# one_wire_com_board.net
KiCad netlist of a schematic drawn in EAGLE
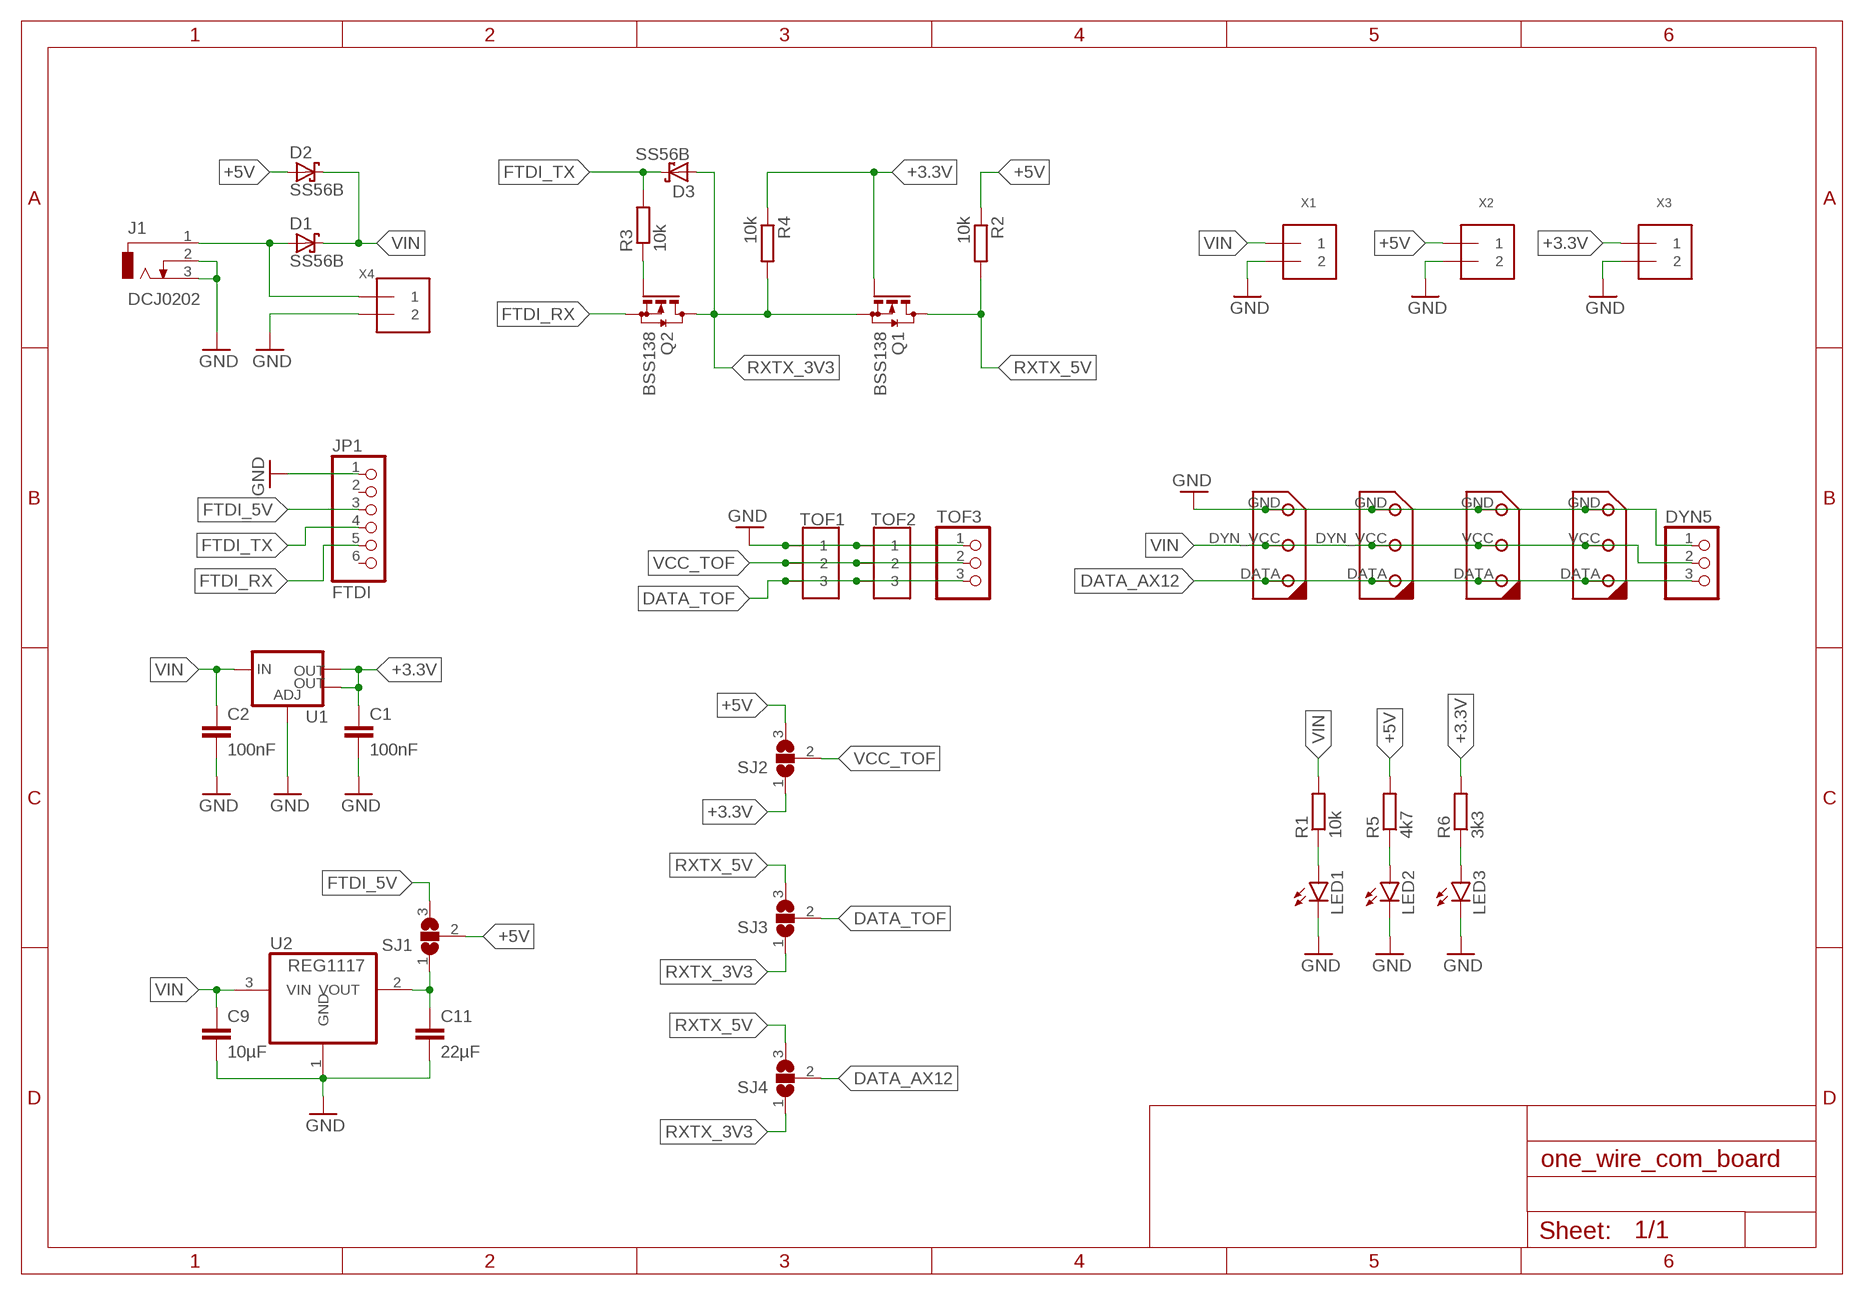
[diagram p0: schematic, sheet 1]

(export (version "E")
  (design (tool "Eeschema 10.0.6"))
  (components
    (comp (ref "C1")
      (value "100nF")
      (footprint "eagle-import:C0805")
      (libsource (lib "eagle-import") (part "C-EUC0805"))
    )
    (comp (ref "C2")
      (value "100nF")
      (footprint "eagle-import:C0805")
      (libsource (lib "eagle-import") (part "C-EUC0805"))
    )
    (comp (ref "C9")
      (value "10µF")
      (footprint "eagle-import:C0805")
      (libsource (lib "eagle-import") (part "resistor_348_C-EUC0805"))
    )
    (comp (ref "C11")
      (value "22µF")
      (footprint "eagle-import:C0805")
      (libsource (lib "eagle-import") (part "resistor_348_C-EUC0805"))
    )
    (comp (ref "D1")
      (value "SS56B")
      (footprint "eagle-import:SMB")
      (libsource (lib "eagle-import") (part "SCHOTTKY-DIODESMD"))
    )
    (comp (ref "D2")
      (value "SS56B")
      (footprint "eagle-import:SMB")
      (libsource (lib "eagle-import") (part "SCHOTTKY-DIODESMD"))
    )
    (comp (ref "D3")
      (value "SS56B")
      (footprint "eagle-import:SMB")
      (libsource (lib "eagle-import") (part "SCHOTTKY-DIODESMD"))
    )
    (comp (ref "DYN1")
      (value "DYNAMIXEL-1X03AX")
      (footprint "eagle-import:DYNAMIXEL_AX_1X03")
      (libsource (lib "eagle-import") (part "DYNAMIXEL-1X03AX"))
    )
    (comp (ref "DYN2")
      (value "DYNAMIXEL-1X03AX")
      (footprint "eagle-import:DYNAMIXEL_AX_1X03")
      (libsource (lib "eagle-import") (part "DYNAMIXEL-1X03AX"))
    )
    (comp (ref "DYN3")
      (value "DYNAMIXEL-1X03XL")
      (footprint "eagle-import:DYNAMIXEL_XL_1X03")
      (libsource (lib "eagle-import") (part "DYNAMIXEL-1X03XL"))
    )
    (comp (ref "DYN4")
      (value "DYNAMIXEL-1X03XL")
      (footprint "eagle-import:DYNAMIXEL_XL_1X03")
      (libsource (lib "eagle-import") (part "DYNAMIXEL-1X03XL"))
    )
    (comp (ref "DYN5")
      (value "PINHD-1X3")
      (footprint "eagle-import:1X03")
      (libsource (lib "eagle-import") (part "PINHD-1X3"))
    )
    (comp (ref "J1")
      (value "DCJ0202")
      (footprint "eagle-import:DCJ0202")
      (libsource (lib "eagle-import") (part "DCJ0202"))
    )
    (comp (ref "JP1")
      (value "FTDI")
      (footprint "eagle-import:1X06_90")
      (libsource (lib "eagle-import") (part "PINHD-1X6/90"))
    )
    (comp (ref "LED1")
      (value "LEDSMT1206")
      (footprint "eagle-import:1206")
      (libsource (lib "eagle-import") (part "LEDSMT1206"))
    )
    (comp (ref "LED2")
      (value "LEDSMT1206")
      (footprint "eagle-import:1206")
      (libsource (lib "eagle-import") (part "LEDSMT1206"))
    )
    (comp (ref "LED3")
      (value "LEDSMT1206")
      (footprint "eagle-import:1206")
      (libsource (lib "eagle-import") (part "LEDSMT1206"))
    )
    (comp (ref "Q1")
      (value "BSS138")
      (footprint "eagle-import:SOT23")
      (libsource (lib "eagle-import") (part "BSS123"))
    )
    (comp (ref "Q2")
      (value "BSS138")
      (footprint "eagle-import:SOT23")
      (libsource (lib "eagle-import") (part "BSS123"))
    )
    (comp (ref "R1")
      (value "10k")
      (footprint "eagle-import:R0805")
      (libsource (lib "eagle-import") (part "R-EU_R0805"))
    )
    (comp (ref "R2")
      (value "10k")
      (footprint "eagle-import:R0805")
      (libsource (lib "eagle-import") (part "R-EU_R0805"))
    )
    (comp (ref "R3")
      (value "10k")
      (footprint "eagle-import:R0805")
      (libsource (lib "eagle-import") (part "R-EU_R0805"))
    )
    (comp (ref "R4")
      (value "10k")
      (footprint "eagle-import:R0805")
      (libsource (lib "eagle-import") (part "R-EU_R0805"))
    )
    (comp (ref "R5")
      (value "4k7")
      (footprint "eagle-import:R0805")
      (libsource (lib "eagle-import") (part "R-EU_R0805"))
    )
    (comp (ref "R6")
      (value "3k3")
      (footprint "eagle-import:R0805")
      (libsource (lib "eagle-import") (part "R-EU_R0805"))
    )
    (comp (ref "SJ1")
      (value "SJ2W")
      (footprint "eagle-import:SJ_2")
      (libsource (lib "eagle-import") (part "SJ2W"))
    )
    (comp (ref "SJ2")
      (value "SJ2W")
      (footprint "eagle-import:SJ_2")
      (libsource (lib "eagle-import") (part "SJ2W"))
    )
    (comp (ref "SJ3")
      (value "SJ2W")
      (footprint "eagle-import:SJ_2")
      (libsource (lib "eagle-import") (part "SJ2W"))
    )
    (comp (ref "SJ4")
      (value "SJ2W")
      (footprint "eagle-import:SJ_2")
      (libsource (lib "eagle-import") (part "SJ2W"))
    )
    (comp (ref "TOF1")
      (value "JST-03")
      (footprint "eagle-import:GH-03-V")
      (libsource (lib "eagle-import") (part "JST-03"))
    )
    (comp (ref "TOF2")
      (value "JST-03")
      (footprint "eagle-import:GH-03-V")
      (libsource (lib "eagle-import") (part "JST-03"))
    )
    (comp (ref "TOF3")
      (value "PINHD-1X3")
      (footprint "eagle-import:1X03")
      (libsource (lib "eagle-import") (part "PINHD-1X3"))
    )
    (comp (ref "U1")
      (value "V_REG_LM1117SOT223")
      (footprint "eagle-import:SOT223")
      (libsource (lib "eagle-import") (part "V_REG_LM1117SOT223"))
    )
    (comp (ref "U2")
      (value "REG1117")
      (footprint "eagle-import:SOT223")
      (libsource (lib "eagle-import") (part "REG1117"))
    )
    (comp (ref "X1")
      (value "TERMBLOCK_1X2")
      (footprint "eagle-import:TERMBLOCK_1X2-3.5MM")
      (libsource (lib "eagle-import") (part "TERMBLOCK_1X2"))
    )
    (comp (ref "X2")
      (value "TERMBLOCK_1X2")
      (footprint "eagle-import:TERMBLOCK_1X2-3.5MM")
      (libsource (lib "eagle-import") (part "TERMBLOCK_1X2"))
    )
    (comp (ref "X3")
      (value "TERMBLOCK_1X2")
      (footprint "eagle-import:TERMBLOCK_1X2-3.5MM")
      (libsource (lib "eagle-import") (part "TERMBLOCK_1X2"))
    )
    (comp (ref "X4")
      (value "TERMBLOCK_1X2")
      (footprint "eagle-import:TERMBLOCK_1X2-3.5MM")
      (libsource (lib "eagle-import") (part "TERMBLOCK_1X2"))
    )
  )
  (nets
    (net (code "1") (name "+3.3V") (class "Default")
      (node (ref "C1") (pin "1") (pinfunction "1_1") (pintype "passive"))
      (node (ref "Q1") (pin "1") (pinfunction "G_1") (pintype "passive"))
      (node (ref "R4") (pin "1") (pinfunction "1_1") (pintype "passive"))
      (node (ref "R6") (pin "2") (pinfunction "2_2") (pintype "passive"))
      (node (ref "SJ2") (pin "1") (pinfunction "1_1") (pintype "passive"))
      (node (ref "U1") (pin "2") (pinfunction "OUT_2") (pintype "output"))
      (node (ref "U1") (pin "4") (pinfunction "OUT_4") (pintype "output"))
      (node (ref "X3") (pin "1") (pinfunction "1_1") (pintype "passive"))
    )
    (net (code "2") (name "+5V") (class "Default")
      (node (ref "D2") (pin "A") (pinfunction "A_A") (pintype "passive"))
      (node (ref "R2") (pin "1") (pinfunction "1_1") (pintype "passive"))
      (node (ref "R5") (pin "2") (pinfunction "2_2") (pintype "passive"))
      (node (ref "SJ1") (pin "2") (pinfunction "2_2") (pintype "passive"))
      (node (ref "SJ2") (pin "3") (pinfunction "3_3") (pintype "passive"))
      (node (ref "X2") (pin "1") (pinfunction "1_1") (pintype "passive"))
    )
    (net (code "3") (name "DATA_AX12") (class "Default")
      (node (ref "DYN1") (pin "DATA") (pinfunction "DATA_DATA") (pintype "bidirectional"))
      (node (ref "DYN2") (pin "DATA") (pinfunction "DATA_DATA") (pintype "bidirectional"))
      (node (ref "DYN3") (pin "DATA") (pinfunction "DATA_DATA") (pintype "bidirectional"))
      (node (ref "DYN4") (pin "DATA") (pinfunction "DATA_DATA") (pintype "bidirectional"))
      (node (ref "DYN5") (pin "3") (pinfunction "3_3") (pintype "passive"))
      (node (ref "SJ4") (pin "2") (pinfunction "2_2") (pintype "passive"))
    )
    (net (code "4") (name "DATA_TOF") (class "Default")
      (node (ref "SJ3") (pin "2") (pinfunction "2_2") (pintype "passive"))
      (node (ref "TOF1") (pin "3") (pinfunction "3_3") (pintype "bidirectional"))
      (node (ref "TOF2") (pin "3") (pinfunction "3_3") (pintype "bidirectional"))
      (node (ref "TOF3") (pin "3") (pinfunction "3_3") (pintype "passive"))
    )
    (net (code "5") (name "FTDI_5V") (class "Default")
      (node (ref "JP1") (pin "3") (pinfunction "3_3") (pintype "passive"))
      (node (ref "SJ1") (pin "3") (pinfunction "3_3") (pintype "passive"))
    )
    (net (code "6") (name "FTDI_RX") (class "Default")
      (node (ref "JP1") (pin "5") (pinfunction "5_5") (pintype "passive"))
      (node (ref "Q2") (pin "2") (pinfunction "S_2") (pintype "passive"))
    )
    (net (code "7") (name "FTDI_TX") (class "Default")
      (node (ref "D3") (pin "C") (pinfunction "C_C") (pintype "passive"))
      (node (ref "JP1") (pin "4") (pinfunction "4_4") (pintype "passive"))
      (node (ref "R3") (pin "2") (pinfunction "2_2") (pintype "passive"))
    )
    (net (code "8") (name "GND") (class "Default")
      (node (ref "C1") (pin "2") (pinfunction "2_2") (pintype "passive"))
      (node (ref "C11") (pin "2") (pinfunction "2_2") (pintype "passive"))
      (node (ref "C2") (pin "2") (pinfunction "2_2") (pintype "passive"))
      (node (ref "C9") (pin "2") (pinfunction "2_2") (pintype "passive"))
      (node (ref "DYN1") (pin "GND") (pinfunction "GND_GND") (pintype "power_in"))
      (node (ref "DYN2") (pin "GND") (pinfunction "GND_GND") (pintype "power_in"))
      (node (ref "DYN3") (pin "GND") (pinfunction "GND_GND") (pintype "power_in"))
      (node (ref "DYN4") (pin "GND") (pinfunction "GND_GND") (pintype "power_in"))
      (node (ref "DYN5") (pin "1") (pinfunction "1_1") (pintype "passive"))
      (node (ref "J1") (pin "2") (pinfunction "2_2") (pintype "passive"))
      (node (ref "J1") (pin "3") (pinfunction "3_3") (pintype "passive"))
      (node (ref "JP1") (pin "1") (pinfunction "1_1") (pintype "passive"))
      (node (ref "LED1") (pin "C") (pinfunction "C_C") (pintype "passive"))
      (node (ref "LED2") (pin "C") (pinfunction "C_C") (pintype "passive"))
      (node (ref "LED3") (pin "C") (pinfunction "C_C") (pintype "passive"))
      (node (ref "TOF1") (pin "1") (pinfunction "1_1") (pintype "bidirectional"))
      (node (ref "TOF2") (pin "1") (pinfunction "1_1") (pintype "bidirectional"))
      (node (ref "TOF3") (pin "1") (pinfunction "1_1") (pintype "passive"))
      (node (ref "U1") (pin "1") (pinfunction "ADJ_1") (pintype "input"))
      (node (ref "U2") (pin "1") (pinfunction "GND_1") (pintype "power_in"))
      (node (ref "X1") (pin "2") (pinfunction "2_2") (pintype "passive"))
      (node (ref "X2") (pin "2") (pinfunction "2_2") (pintype "passive"))
      (node (ref "X3") (pin "2") (pinfunction "2_2") (pintype "passive"))
      (node (ref "X4") (pin "2") (pinfunction "2_2") (pintype "passive"))
    )
    (net (code "9") (name "Net-(D1-PadA)") (class "Default")
      (node (ref "D1") (pin "A") (pinfunction "A_A") (pintype "passive"))
      (node (ref "J1") (pin "1") (pinfunction "1_1") (pintype "passive"))
      (node (ref "X4") (pin "1") (pinfunction "1_1") (pintype "passive"))
    )
    (net (code "10") (name "Net-(LED1-PadA)") (class "Default")
      (node (ref "LED1") (pin "A") (pinfunction "A_A") (pintype "passive"))
      (node (ref "R1") (pin "1") (pinfunction "1_1") (pintype "passive"))
    )
    (net (code "11") (name "Net-(LED2-PadA)") (class "Default")
      (node (ref "LED2") (pin "A") (pinfunction "A_A") (pintype "passive"))
      (node (ref "R5") (pin "1") (pinfunction "1_1") (pintype "passive"))
    )
    (net (code "12") (name "Net-(LED3-PadA)") (class "Default")
      (node (ref "LED3") (pin "A") (pinfunction "A_A") (pintype "passive"))
      (node (ref "R6") (pin "1") (pinfunction "1_1") (pintype "passive"))
    )
    (net (code "13") (name "Net-(Q2-G)") (class "Default")
      (node (ref "Q2") (pin "1") (pinfunction "G_1") (pintype "passive"))
      (node (ref "R3") (pin "1") (pinfunction "1_1") (pintype "passive"))
    )
    (net (code "14") (name "Net-(U2-VOUT)") (class "Default")
      (node (ref "C11") (pin "1") (pinfunction "1_1") (pintype "passive"))
      (node (ref "SJ1") (pin "1") (pinfunction "1_1") (pintype "passive"))
      (node (ref "U2") (pin "2") (pinfunction "VOUT_2") (pintype "output"))
    )
    (net (code "15") (name "RXTX_3V3") (class "Default")
      (node (ref "D3") (pin "A") (pinfunction "A_A") (pintype "passive"))
      (node (ref "Q1") (pin "2") (pinfunction "S_2") (pintype "passive"))
      (node (ref "Q2") (pin "3") (pinfunction "D_3") (pintype "passive"))
      (node (ref "R4") (pin "2") (pinfunction "2_2") (pintype "passive"))
      (node (ref "SJ3") (pin "1") (pinfunction "1_1") (pintype "passive"))
      (node (ref "SJ4") (pin "1") (pinfunction "1_1") (pintype "passive"))
    )
    (net (code "16") (name "RXTX_5V") (class "Default")
      (node (ref "Q1") (pin "3") (pinfunction "D_3") (pintype "passive"))
      (node (ref "R2") (pin "2") (pinfunction "2_2") (pintype "passive"))
      (node (ref "SJ3") (pin "3") (pinfunction "3_3") (pintype "passive"))
      (node (ref "SJ4") (pin "3") (pinfunction "3_3") (pintype "passive"))
    )
    (net (code "17") (name "VCC_TOF") (class "Default")
      (node (ref "SJ2") (pin "2") (pinfunction "2_2") (pintype "passive"))
      (node (ref "TOF1") (pin "2") (pinfunction "2_2") (pintype "bidirectional"))
      (node (ref "TOF2") (pin "2") (pinfunction "2_2") (pintype "bidirectional"))
      (node (ref "TOF3") (pin "2") (pinfunction "2_2") (pintype "passive"))
    )
    (net (code "18") (name "VIN") (class "Default")
      (node (ref "C2") (pin "1") (pinfunction "1_1") (pintype "passive"))
      (node (ref "C9") (pin "1") (pinfunction "1_1") (pintype "passive"))
      (node (ref "D1") (pin "C") (pinfunction "C_C") (pintype "passive"))
      (node (ref "D2") (pin "C") (pinfunction "C_C") (pintype "passive"))
      (node (ref "DYN1") (pin "DYN_VCC") (pinfunction "DYN_VCC_DYN_VCC") (pintype "power_in"))
      (node (ref "DYN2") (pin "DYN_VCC") (pinfunction "DYN_VCC_DYN_VCC") (pintype "power_in"))
      (node (ref "DYN3") (pin "VCC") (pinfunction "DYN_VCC_VCC") (pintype "power_in"))
      (node (ref "DYN4") (pin "VCC") (pinfunction "DYN_VCC_VCC") (pintype "power_in"))
      (node (ref "DYN5") (pin "2") (pinfunction "2_2") (pintype "passive"))
      (node (ref "R1") (pin "2") (pinfunction "2_2") (pintype "passive"))
      (node (ref "U1") (pin "3") (pinfunction "IN_3") (pintype "input"))
      (node (ref "U2") (pin "3") (pinfunction "VIN_3") (pintype "input"))
      (node (ref "X1") (pin "1") (pinfunction "1_1") (pintype "passive"))
    )
    (net (code "19") (name "unconnected-(JP1-Pad2)") (class "Default")
      (node (ref "JP1") (pin "2") (pinfunction "2_2") (pintype "passive"))
    )
    (net (code "20") (name "unconnected-(JP1-Pad6)") (class "Default")
      (node (ref "JP1") (pin "6") (pinfunction "6_6") (pintype "passive"))
    )
  )
)
